# Mako_DSP_Memory_R2_1.net
KiCad netlist of a schematic drawn in Altium Designer
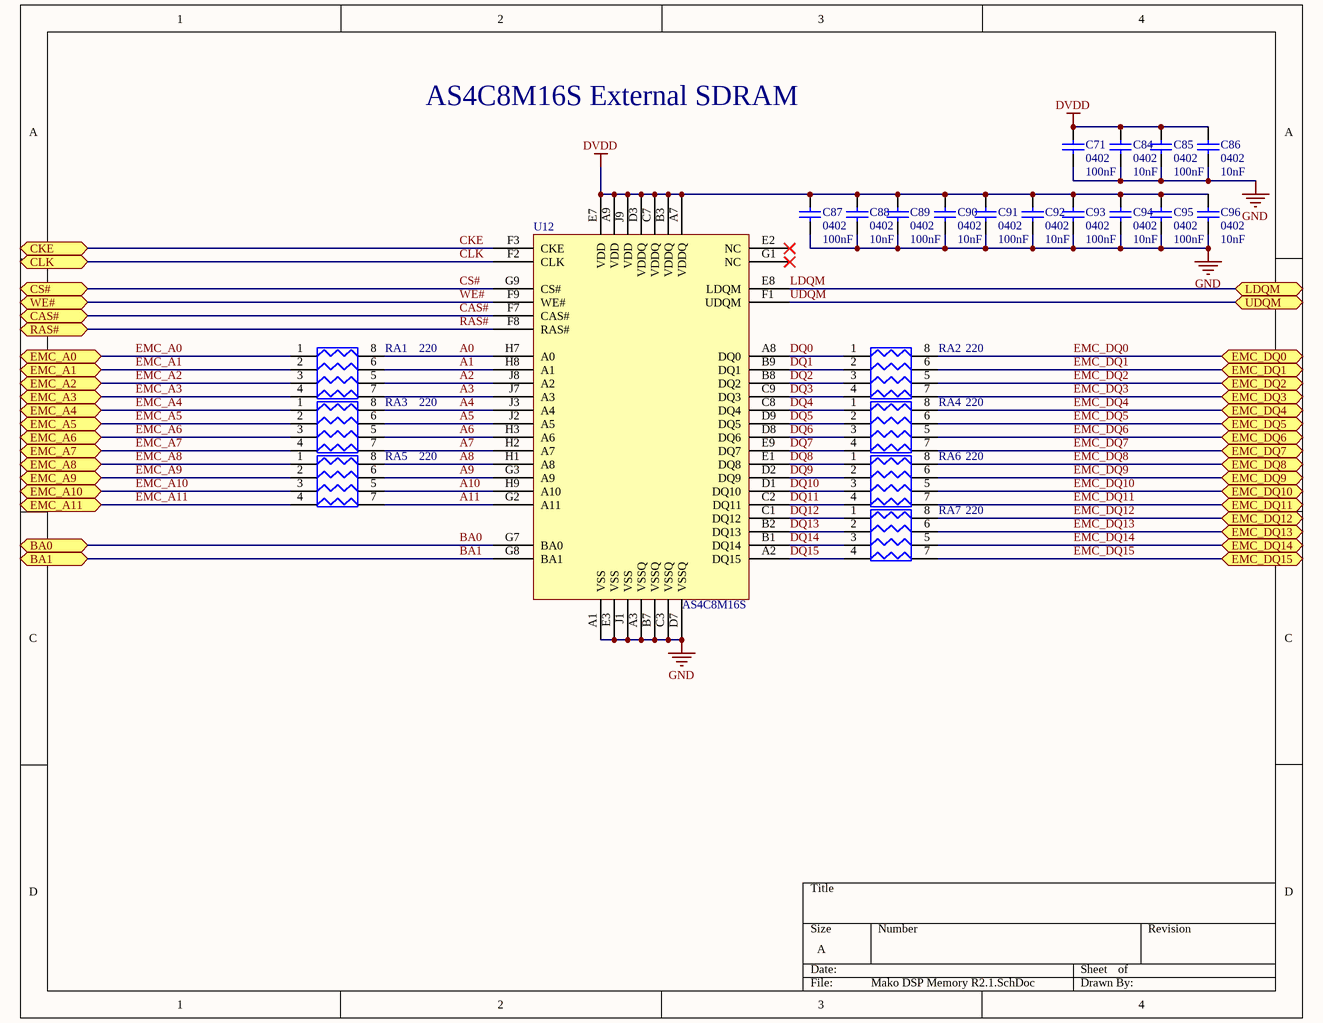
[diagram p0: Mako DSP Memory R2.1.SchDoc]

(export (version "E")
  (design (tool "Eeschema 10.0.6"))
  (components
    (comp (ref "C71")
      (value "0402")
      (footprint "0402")
      (description "Capacitor (Semiconductor SIM Model)")
      (fields (field (name "ALTIUM_VALUE") "100nF") (field (name "PUBLISHER") "Altium Limited"))
      (libsource (lib "Miscellaneous Devices") (part "Cap Semi"))
    )
    (comp (ref "C84")
      (value "0402")
      (footprint "0402")
      (description "Capacitor (Semiconductor SIM Model)")
      (fields (field (name "ALTIUM_VALUE") "10nF") (field (name "PUBLISHER") "Altium Limited"))
      (libsource (lib "Miscellaneous Devices") (part "Cap Semi"))
    )
    (comp (ref "C85")
      (value "0402")
      (footprint "0402")
      (description "Capacitor (Semiconductor SIM Model)")
      (fields (field (name "ALTIUM_VALUE") "100nF") (field (name "PUBLISHER") "Altium Limited"))
      (libsource (lib "Miscellaneous Devices") (part "Cap Semi"))
    )
    (comp (ref "C86")
      (value "0402")
      (footprint "0402")
      (description "Capacitor (Semiconductor SIM Model)")
      (fields (field (name "ALTIUM_VALUE") "10nF") (field (name "PUBLISHER") "Altium Limited"))
      (libsource (lib "Miscellaneous Devices") (part "Cap Semi"))
    )
    (comp (ref "C87")
      (value "0402")
      (footprint "0402")
      (description "Capacitor (Semiconductor SIM Model)")
      (fields (field (name "ALTIUM_VALUE") "100nF") (field (name "PUBLISHER") "Altium Limited"))
      (libsource (lib "Miscellaneous Devices") (part "Cap Semi"))
    )
    (comp (ref "C88")
      (value "0402")
      (footprint "0402")
      (description "Capacitor (Semiconductor SIM Model)")
      (fields (field (name "ALTIUM_VALUE") "10nF") (field (name "PUBLISHER") "Altium Limited"))
      (libsource (lib "Miscellaneous Devices") (part "Cap Semi"))
    )
    (comp (ref "C89")
      (value "0402")
      (footprint "0402")
      (description "Capacitor (Semiconductor SIM Model)")
      (fields (field (name "ALTIUM_VALUE") "100nF") (field (name "PUBLISHER") "Altium Limited"))
      (libsource (lib "Miscellaneous Devices") (part "Cap Semi"))
    )
    (comp (ref "C90")
      (value "0402")
      (footprint "0402")
      (description "Capacitor (Semiconductor SIM Model)")
      (fields (field (name "ALTIUM_VALUE") "10nF") (field (name "PUBLISHER") "Altium Limited"))
      (libsource (lib "Miscellaneous Devices") (part "Cap Semi"))
    )
    (comp (ref "C91")
      (value "0402")
      (footprint "0402")
      (description "Capacitor (Semiconductor SIM Model)")
      (fields (field (name "ALTIUM_VALUE") "100nF") (field (name "PUBLISHER") "Altium Limited"))
      (libsource (lib "Miscellaneous Devices") (part "Cap Semi"))
    )
    (comp (ref "C92")
      (value "0402")
      (footprint "0402")
      (description "Capacitor (Semiconductor SIM Model)")
      (fields (field (name "ALTIUM_VALUE") "10nF") (field (name "PUBLISHER") "Altium Limited"))
      (libsource (lib "Miscellaneous Devices") (part "Cap Semi"))
    )
    (comp (ref "C93")
      (value "0402")
      (footprint "0402")
      (description "Capacitor (Semiconductor SIM Model)")
      (fields (field (name "ALTIUM_VALUE") "100nF") (field (name "PUBLISHER") "Altium Limited"))
      (libsource (lib "Miscellaneous Devices") (part "Cap Semi"))
    )
    (comp (ref "C94")
      (value "0402")
      (footprint "0402")
      (description "Capacitor (Semiconductor SIM Model)")
      (fields (field (name "ALTIUM_VALUE") "10nF") (field (name "PUBLISHER") "Altium Limited"))
      (libsource (lib "Miscellaneous Devices") (part "Cap Semi"))
    )
    (comp (ref "C95")
      (value "0402")
      (footprint "0402")
      (description "Capacitor (Semiconductor SIM Model)")
      (fields (field (name "ALTIUM_VALUE") "100nF") (field (name "PUBLISHER") "Altium Limited"))
      (libsource (lib "Miscellaneous Devices") (part "Cap Semi"))
    )
    (comp (ref "C96")
      (value "0402")
      (footprint "0402")
      (description "Capacitor (Semiconductor SIM Model)")
      (fields (field (name "ALTIUM_VALUE") "10nF") (field (name "PUBLISHER") "Altium Limited"))
      (libsource (lib "Miscellaneous Devices") (part "Cap Semi"))
    )
    (comp (ref "RA1")
      (value "220")
      (footprint "742C083")
      (description "Resistor array")
      (fields (field (name "Comment") "RESISTOR ARRAY"))
      (libsource (lib "Mako DSP Schematic Library") (part "RESISTOR ARRAY"))
    )
    (comp (ref "RA2")
      (value "220")
      (footprint "742C083")
      (description "Resistor array")
      (fields (field (name "Comment") "RESISTOR ARRAY"))
      (libsource (lib "Mako DSP Schematic Library") (part "RESISTOR ARRAY"))
    )
    (comp (ref "RA3")
      (value "220")
      (footprint "742C083")
      (description "Resistor array")
      (fields (field (name "Comment") "RESISTOR ARRAY"))
      (libsource (lib "Mako DSP Schematic Library") (part "RESISTOR ARRAY"))
    )
    (comp (ref "RA4")
      (value "220")
      (footprint "742C083")
      (description "Resistor array")
      (fields (field (name "Comment") "RESISTOR ARRAY"))
      (libsource (lib "Mako DSP Schematic Library") (part "RESISTOR ARRAY"))
    )
    (comp (ref "RA5")
      (value "220")
      (footprint "742C083")
      (description "Resistor array")
      (fields (field (name "Comment") "RESISTOR ARRAY"))
      (libsource (lib "Mako DSP Schematic Library") (part "RESISTOR ARRAY"))
    )
    (comp (ref "RA6")
      (value "220")
      (footprint "742C083")
      (description "Resistor array")
      (fields (field (name "Comment") "RESISTOR ARRAY"))
      (libsource (lib "Mako DSP Schematic Library") (part "RESISTOR ARRAY"))
    )
    (comp (ref "RA7")
      (value "220")
      (footprint "742C083")
      (description "Resistor array")
      (fields (field (name "Comment") "RESISTOR ARRAY"))
      (libsource (lib "Mako DSP Schematic Library") (part "RESISTOR ARRAY"))
    )
    (comp (ref "U12")
      (value "AS4C8M16S")
      (footprint "AS4C8M16S")
      (libsource (lib "Mako DSP Schematic Library") (part "AS4C8M16S"))
    )
  )
  (nets
    (net (code "1") (name "/A0") (class "Default")
      (node (ref "RA1") (pin "8") (pinfunction "8_8") (pintype "passive"))
      (node (ref "U12") (pin "H7") (pinfunction "A0_H7") (pintype "passive"))
    )
    (net (code "2") (name "/A1") (class "Default")
      (node (ref "RA1") (pin "6") (pinfunction "6_6") (pintype "passive"))
      (node (ref "U12") (pin "H8") (pinfunction "A1_H8") (pintype "passive"))
    )
    (net (code "3") (name "/A2") (class "Default")
      (node (ref "RA1") (pin "5") (pinfunction "5_5") (pintype "passive"))
      (node (ref "U12") (pin "J8") (pinfunction "A2_J8") (pintype "passive"))
    )
    (net (code "4") (name "/A3") (class "Default")
      (node (ref "RA1") (pin "7") (pinfunction "7_7") (pintype "passive"))
      (node (ref "U12") (pin "J7") (pinfunction "A3_J7") (pintype "passive"))
    )
    (net (code "5") (name "/A4") (class "Default")
      (node (ref "RA3") (pin "8") (pinfunction "8_8") (pintype "passive"))
      (node (ref "U12") (pin "J3") (pinfunction "A4_J3") (pintype "passive"))
    )
    (net (code "6") (name "/A5") (class "Default")
      (node (ref "RA3") (pin "6") (pinfunction "6_6") (pintype "passive"))
      (node (ref "U12") (pin "J2") (pinfunction "A5_J2") (pintype "passive"))
    )
    (net (code "7") (name "/A6") (class "Default")
      (node (ref "RA3") (pin "5") (pinfunction "5_5") (pintype "passive"))
      (node (ref "U12") (pin "H3") (pinfunction "A6_H3") (pintype "passive"))
    )
    (net (code "8") (name "/A7") (class "Default")
      (node (ref "RA3") (pin "7") (pinfunction "7_7") (pintype "passive"))
      (node (ref "U12") (pin "H2") (pinfunction "A7_H2") (pintype "passive"))
    )
    (net (code "9") (name "/A8") (class "Default")
      (node (ref "RA5") (pin "8") (pinfunction "8_8") (pintype "passive"))
      (node (ref "U12") (pin "H1") (pinfunction "A8_H1") (pintype "passive"))
    )
    (net (code "10") (name "/A9") (class "Default")
      (node (ref "RA5") (pin "6") (pinfunction "6_6") (pintype "passive"))
      (node (ref "U12") (pin "G3") (pinfunction "A9_G3") (pintype "passive"))
    )
    (net (code "11") (name "/A10") (class "Default")
      (node (ref "RA5") (pin "5") (pinfunction "5_5") (pintype "passive"))
      (node (ref "U12") (pin "H9") (pinfunction "A10_H9") (pintype "passive"))
    )
    (net (code "12") (name "/A11") (class "Default")
      (node (ref "RA5") (pin "7") (pinfunction "7_7") (pintype "passive"))
      (node (ref "U12") (pin "G2") (pinfunction "A11_G2") (pintype "passive"))
    )
    (net (code "13") (name "/BA0") (class "Default")
      (node (ref "U12") (pin "G7") (pinfunction "BA0_G7") (pintype "passive"))
    )
    (net (code "14") (name "/BA1") (class "Default")
      (node (ref "U12") (pin "G8") (pinfunction "BA1_G8") (pintype "passive"))
    )
    (net (code "15") (name "/CAS#") (class "Default")
      (node (ref "U12") (pin "F7") (pinfunction "CAS#_F7") (pintype "passive"))
    )
    (net (code "16") (name "/CKE") (class "Default")
      (node (ref "U12") (pin "F3") (pinfunction "CKE_F3") (pintype "passive"))
    )
    (net (code "17") (name "/CLK") (class "Default")
      (node (ref "U12") (pin "F2") (pinfunction "CLK_F2") (pintype "passive"))
    )
    (net (code "18") (name "/CS#") (class "Default")
      (node (ref "U12") (pin "G9") (pinfunction "CS#_G9") (pintype "passive"))
    )
    (net (code "19") (name "/DQ0") (class "Default")
      (node (ref "RA2") (pin "1") (pinfunction "1_1") (pintype "passive"))
      (node (ref "U12") (pin "A8") (pinfunction "DQ0_A8") (pintype "passive"))
    )
    (net (code "20") (name "/DQ1") (class "Default")
      (node (ref "RA2") (pin "2") (pinfunction "2_2") (pintype "passive"))
      (node (ref "U12") (pin "B9") (pinfunction "DQ1_B9") (pintype "passive"))
    )
    (net (code "21") (name "/DQ2") (class "Default")
      (node (ref "RA2") (pin "3") (pinfunction "3_3") (pintype "passive"))
      (node (ref "U12") (pin "B8") (pinfunction "DQ2_B8") (pintype "passive"))
    )
    (net (code "22") (name "/DQ3") (class "Default")
      (node (ref "RA2") (pin "4") (pinfunction "4_4") (pintype "passive"))
      (node (ref "U12") (pin "C9") (pinfunction "DQ3_C9") (pintype "passive"))
    )
    (net (code "23") (name "/DQ4") (class "Default")
      (node (ref "RA4") (pin "1") (pinfunction "1_1") (pintype "passive"))
      (node (ref "U12") (pin "C8") (pinfunction "DQ4_C8") (pintype "passive"))
    )
    (net (code "24") (name "/DQ5") (class "Default")
      (node (ref "RA4") (pin "2") (pinfunction "2_2") (pintype "passive"))
      (node (ref "U12") (pin "D9") (pinfunction "DQ5_D9") (pintype "passive"))
    )
    (net (code "25") (name "/DQ6") (class "Default")
      (node (ref "RA4") (pin "3") (pinfunction "3_3") (pintype "passive"))
      (node (ref "U12") (pin "D8") (pinfunction "DQ6_D8") (pintype "passive"))
    )
    (net (code "26") (name "/DQ7") (class "Default")
      (node (ref "RA4") (pin "4") (pinfunction "4_4") (pintype "passive"))
      (node (ref "U12") (pin "E9") (pinfunction "DQ7_E9") (pintype "passive"))
    )
    (net (code "27") (name "/DQ8") (class "Default")
      (node (ref "RA6") (pin "1") (pinfunction "1_1") (pintype "passive"))
      (node (ref "U12") (pin "E1") (pinfunction "DQ8_E1") (pintype "passive"))
    )
    (net (code "28") (name "/DQ9") (class "Default")
      (node (ref "RA6") (pin "2") (pinfunction "2_2") (pintype "passive"))
      (node (ref "U12") (pin "D2") (pinfunction "DQ9_D2") (pintype "passive"))
    )
    (net (code "29") (name "/DQ10") (class "Default")
      (node (ref "RA6") (pin "3") (pinfunction "3_3") (pintype "passive"))
      (node (ref "U12") (pin "D1") (pinfunction "DQ10_D1") (pintype "passive"))
    )
    (net (code "30") (name "/DQ11") (class "Default")
      (node (ref "RA6") (pin "4") (pinfunction "4_4") (pintype "passive"))
      (node (ref "U12") (pin "C2") (pinfunction "DQ11_C2") (pintype "passive"))
    )
    (net (code "31") (name "/DQ12") (class "Default")
      (node (ref "RA7") (pin "1") (pinfunction "1_1") (pintype "passive"))
      (node (ref "U12") (pin "C1") (pinfunction "DQ12_C1") (pintype "passive"))
    )
    (net (code "32") (name "/DQ13") (class "Default")
      (node (ref "RA7") (pin "2") (pinfunction "2_2") (pintype "passive"))
      (node (ref "U12") (pin "B2") (pinfunction "DQ13_B2") (pintype "passive"))
    )
    (net (code "33") (name "/DQ14") (class "Default")
      (node (ref "RA7") (pin "3") (pinfunction "3_3") (pintype "passive"))
      (node (ref "U12") (pin "B1") (pinfunction "DQ14_B1") (pintype "passive"))
    )
    (net (code "34") (name "/DQ15") (class "Default")
      (node (ref "RA7") (pin "4") (pinfunction "4_4") (pintype "passive"))
      (node (ref "U12") (pin "A2") (pinfunction "DQ15_A2") (pintype "passive"))
    )
    (net (code "35") (name "/EMC_A0") (class "Default")
      (node (ref "RA1") (pin "1") (pinfunction "1_1") (pintype "passive"))
    )
    (net (code "36") (name "/EMC_A1") (class "Default")
      (node (ref "RA1") (pin "2") (pinfunction "2_2") (pintype "passive"))
    )
    (net (code "37") (name "/EMC_A2") (class "Default")
      (node (ref "RA1") (pin "3") (pinfunction "3_3") (pintype "passive"))
    )
    (net (code "38") (name "/EMC_A3") (class "Default")
      (node (ref "RA1") (pin "4") (pinfunction "4_4") (pintype "passive"))
    )
    (net (code "39") (name "/EMC_A4") (class "Default")
      (node (ref "RA3") (pin "1") (pinfunction "1_1") (pintype "passive"))
    )
    (net (code "40") (name "/EMC_A5") (class "Default")
      (node (ref "RA3") (pin "2") (pinfunction "2_2") (pintype "passive"))
    )
    (net (code "41") (name "/EMC_A6") (class "Default")
      (node (ref "RA3") (pin "3") (pinfunction "3_3") (pintype "passive"))
    )
    (net (code "42") (name "/EMC_A7") (class "Default")
      (node (ref "RA3") (pin "4") (pinfunction "4_4") (pintype "passive"))
    )
    (net (code "43") (name "/EMC_A8") (class "Default")
      (node (ref "RA5") (pin "1") (pinfunction "1_1") (pintype "passive"))
    )
    (net (code "44") (name "/EMC_A9") (class "Default")
      (node (ref "RA5") (pin "2") (pinfunction "2_2") (pintype "passive"))
    )
    (net (code "45") (name "/EMC_A10") (class "Default")
      (node (ref "RA5") (pin "3") (pinfunction "3_3") (pintype "passive"))
    )
    (net (code "46") (name "/EMC_A11") (class "Default")
      (node (ref "RA5") (pin "4") (pinfunction "4_4") (pintype "passive"))
    )
    (net (code "47") (name "/EMC_DQ0") (class "Default")
      (node (ref "RA2") (pin "8") (pinfunction "8_8") (pintype "passive"))
    )
    (net (code "48") (name "/EMC_DQ1") (class "Default")
      (node (ref "RA2") (pin "6") (pinfunction "6_6") (pintype "passive"))
    )
    (net (code "49") (name "/EMC_DQ2") (class "Default")
      (node (ref "RA2") (pin "5") (pinfunction "5_5") (pintype "passive"))
    )
    (net (code "50") (name "/EMC_DQ3") (class "Default")
      (node (ref "RA2") (pin "7") (pinfunction "7_7") (pintype "passive"))
    )
    (net (code "51") (name "/EMC_DQ4") (class "Default")
      (node (ref "RA4") (pin "8") (pinfunction "8_8") (pintype "passive"))
    )
    (net (code "52") (name "/EMC_DQ5") (class "Default")
      (node (ref "RA4") (pin "6") (pinfunction "6_6") (pintype "passive"))
    )
    (net (code "53") (name "/EMC_DQ6") (class "Default")
      (node (ref "RA4") (pin "5") (pinfunction "5_5") (pintype "passive"))
    )
    (net (code "54") (name "/EMC_DQ7") (class "Default")
      (node (ref "RA4") (pin "7") (pinfunction "7_7") (pintype "passive"))
    )
    (net (code "55") (name "/EMC_DQ8") (class "Default")
      (node (ref "RA6") (pin "8") (pinfunction "8_8") (pintype "passive"))
    )
    (net (code "56") (name "/EMC_DQ9") (class "Default")
      (node (ref "RA6") (pin "6") (pinfunction "6_6") (pintype "passive"))
    )
    (net (code "57") (name "/EMC_DQ10") (class "Default")
      (node (ref "RA6") (pin "5") (pinfunction "5_5") (pintype "passive"))
    )
    (net (code "58") (name "/EMC_DQ11") (class "Default")
      (node (ref "RA6") (pin "7") (pinfunction "7_7") (pintype "passive"))
    )
    (net (code "59") (name "/EMC_DQ12") (class "Default")
      (node (ref "RA7") (pin "8") (pinfunction "8_8") (pintype "passive"))
    )
    (net (code "60") (name "/EMC_DQ13") (class "Default")
      (node (ref "RA7") (pin "6") (pinfunction "6_6") (pintype "passive"))
    )
    (net (code "61") (name "/EMC_DQ14") (class "Default")
      (node (ref "RA7") (pin "5") (pinfunction "5_5") (pintype "passive"))
    )
    (net (code "62") (name "/EMC_DQ15") (class "Default")
      (node (ref "RA7") (pin "7") (pinfunction "7_7") (pintype "passive"))
    )
    (net (code "63") (name "/LDQM") (class "Default")
      (node (ref "U12") (pin "E8") (pinfunction "LDQM_E8") (pintype "passive"))
    )
    (net (code "64") (name "/RAS#") (class "Default")
      (node (ref "U12") (pin "F8") (pinfunction "RAS#_F8") (pintype "passive"))
    )
    (net (code "65") (name "/UDQM") (class "Default")
      (node (ref "U12") (pin "F1") (pinfunction "UDQM_F1") (pintype "passive"))
    )
    (net (code "66") (name "/WE#") (class "Default")
      (node (ref "U12") (pin "F9") (pinfunction "WE#_F9") (pintype "passive"))
    )
    (net (code "67") (name "DVDD") (class "Default")
      (node (ref "C71") (pin "2") (pinfunction "2_2") (pintype "passive"))
      (node (ref "C84") (pin "2") (pinfunction "2_2") (pintype "passive"))
      (node (ref "C85") (pin "2") (pinfunction "2_2") (pintype "passive"))
      (node (ref "C86") (pin "2") (pinfunction "2_2") (pintype "passive"))
      (node (ref "C87") (pin "2") (pinfunction "2_2") (pintype "passive"))
      (node (ref "C88") (pin "2") (pinfunction "2_2") (pintype "passive"))
      (node (ref "C89") (pin "2") (pinfunction "2_2") (pintype "passive"))
      (node (ref "C90") (pin "2") (pinfunction "2_2") (pintype "passive"))
      (node (ref "C91") (pin "2") (pinfunction "2_2") (pintype "passive"))
      (node (ref "C92") (pin "2") (pinfunction "2_2") (pintype "passive"))
      (node (ref "C93") (pin "2") (pinfunction "2_2") (pintype "passive"))
      (node (ref "C94") (pin "2") (pinfunction "2_2") (pintype "passive"))
      (node (ref "C95") (pin "2") (pinfunction "2_2") (pintype "passive"))
      (node (ref "C96") (pin "2") (pinfunction "2_2") (pintype "passive"))
      (node (ref "U12") (pin "A7") (pinfunction "VDDQ_A7") (pintype "passive"))
      (node (ref "U12") (pin "A9") (pinfunction "VDD_A9") (pintype "passive"))
      (node (ref "U12") (pin "B3") (pinfunction "VDDQ_B3") (pintype "passive"))
      (node (ref "U12") (pin "C7") (pinfunction "VDDQ_C7") (pintype "passive"))
      (node (ref "U12") (pin "D3") (pinfunction "VDDQ_D3") (pintype "passive"))
      (node (ref "U12") (pin "E7") (pinfunction "VDD_E7") (pintype "passive"))
      (node (ref "U12") (pin "J9") (pinfunction "VDD_J9") (pintype "passive"))
    )
    (net (code "68") (name "GND") (class "Default")
      (node (ref "C71") (pin "1") (pinfunction "1_1") (pintype "passive"))
      (node (ref "C84") (pin "1") (pinfunction "1_1") (pintype "passive"))
      (node (ref "C85") (pin "1") (pinfunction "1_1") (pintype "passive"))
      (node (ref "C86") (pin "1") (pinfunction "1_1") (pintype "passive"))
      (node (ref "C87") (pin "1") (pinfunction "1_1") (pintype "passive"))
      (node (ref "C88") (pin "1") (pinfunction "1_1") (pintype "passive"))
      (node (ref "C89") (pin "1") (pinfunction "1_1") (pintype "passive"))
      (node (ref "C90") (pin "1") (pinfunction "1_1") (pintype "passive"))
      (node (ref "C91") (pin "1") (pinfunction "1_1") (pintype "passive"))
      (node (ref "C92") (pin "1") (pinfunction "1_1") (pintype "passive"))
      (node (ref "C93") (pin "1") (pinfunction "1_1") (pintype "passive"))
      (node (ref "C94") (pin "1") (pinfunction "1_1") (pintype "passive"))
      (node (ref "C95") (pin "1") (pinfunction "1_1") (pintype "passive"))
      (node (ref "C96") (pin "1") (pinfunction "1_1") (pintype "passive"))
      (node (ref "U12") (pin "A1") (pinfunction "VSS_A1") (pintype "passive"))
      (node (ref "U12") (pin "A3") (pinfunction "VSSQ_A3") (pintype "passive"))
      (node (ref "U12") (pin "B7") (pinfunction "VSSQ_B7") (pintype "passive"))
      (node (ref "U12") (pin "C3") (pinfunction "VSSQ_C3") (pintype "passive"))
      (node (ref "U12") (pin "D7") (pinfunction "VSSQ_D7") (pintype "passive"))
      (node (ref "U12") (pin "E3") (pinfunction "VSS_E3") (pintype "passive"))
      (node (ref "U12") (pin "J1") (pinfunction "VSS_J1") (pintype "passive"))
    )
    (net (code "69") (name "unconnected-(U12-NC-PadE2)") (class "Default")
      (node (ref "U12") (pin "E2") (pinfunction "NC_E2") (pintype "passive+no_connect"))
    )
    (net (code "70") (name "unconnected-(U12-NC-PadG1)") (class "Default")
      (node (ref "U12") (pin "G1") (pinfunction "NC_G1") (pintype "passive+no_connect"))
    )
  )
)
